# TinkerAccess_RFID_Adapter.net
KiCad netlist of a schematic drawn in EAGLE
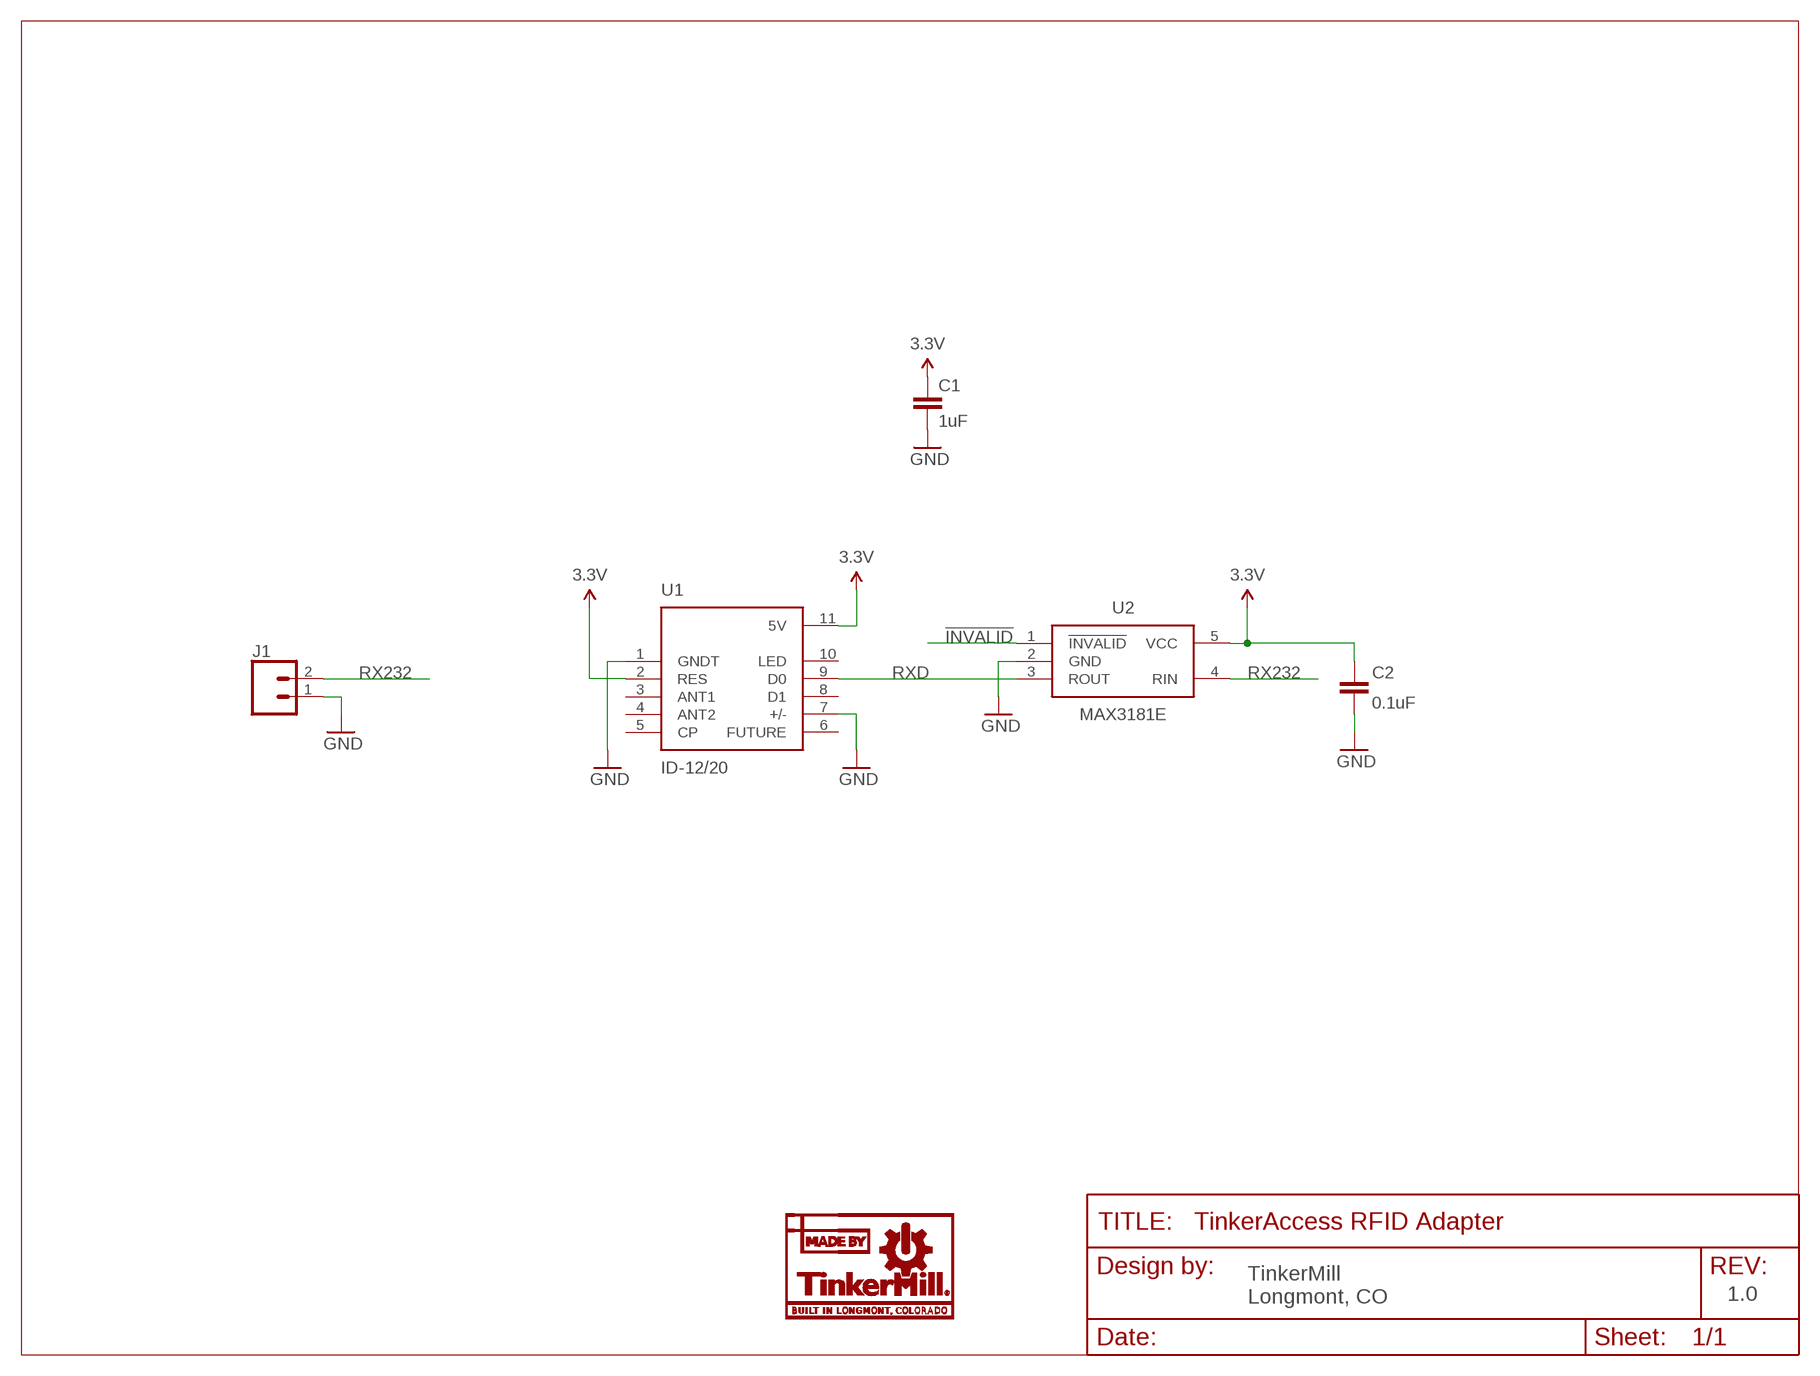
[diagram p0: schematic, sheet 1]

(export (version "E")
  (design (tool "Eeschema 10.0.6"))
  (components
    (comp (ref "C1")
      (value "1uF")
      (footprint "eagle-import:0603")
      (libsource (lib "eagle-import") (part "10UF-0603-6.3V-20%"))
    )
    (comp (ref "C2")
      (value "0.1uF")
      (footprint "eagle-import:0603")
      (fields (field (name "SPICEPREFIX") "C"))
      (libsource (lib "eagle-import") (part "0.1UF-0603-25V-(+80/-20%)"))
    )
    (comp (ref "J1")
      (value "CONN_025MM")
      (footprint "eagle-import:SCREWTERMINAL-5MM-2")
      (libsource (lib "eagle-import") (part "CONN_025MM"))
    )
    (comp (ref "LOGO1")
      (value "MADE_BY_TINKERMILL")
      (footprint "eagle-import:MADE_BY_TINKERMILL")
      (libsource (lib "eagle-import") (part "MADE_BY_TINKERMILL"))
    )
    (comp (ref "U1")
      (value "ID-12/20")
      (footprint "eagle-import:ID-12")
      (libsource (lib "eagle-import") (part "ID-12/20"))
    )
    (comp (ref "U2")
      (value "MAX3181E")
      (footprint "eagle-import:SOT23-5")
      (fields (field (name "SPICEPREFIX") "X"))
      (libsource (lib "eagle-import") (part "MAX3181E_SOT23-5"))
    )
  )
  (nets
    (net (code "1") (name "/RX232") (class "Default")
      (node (ref "J1") (pin "2") (pinfunction "2_2") (pintype "passive"))
      (node (ref "U2") (pin "4") (pinfunction "RIN_4") (pintype "bidirectional"))
    )
    (net (code "2") (name "/RXD") (class "Default")
      (node (ref "U1") (pin "9") (pinfunction "D0_9") (pintype "bidirectional"))
      (node (ref "U2") (pin "3") (pinfunction "ROUT_3") (pintype "bidirectional"))
    )
    (net (code "3") (name "/~{INVALID}") (class "Default")
      (node (ref "U2") (pin "1") (pinfunction "~{INVALID}_1") (pintype "bidirectional"))
    )
    (net (code "4") (name "3.3V") (class "Default")
      (node (ref "C1") (pin "1") (pinfunction "1_1") (pintype "passive"))
      (node (ref "C2") (pin "2") (pinfunction "2_2") (pintype "passive"))
      (node (ref "U1") (pin "11") (pinfunction "5V_11") (pintype "bidirectional"))
      (node (ref "U1") (pin "2") (pinfunction "RES_2") (pintype "bidirectional"))
      (node (ref "U2") (pin "5") (pinfunction "VCC_5") (pintype "bidirectional"))
    )
    (net (code "5") (name "GND") (class "Default")
      (node (ref "C1") (pin "2") (pinfunction "2_2") (pintype "passive"))
      (node (ref "C2") (pin "1") (pinfunction "1_1") (pintype "passive"))
      (node (ref "J1") (pin "1") (pinfunction "1_1") (pintype "passive"))
      (node (ref "U1") (pin "1") (pinfunction "GNDT_1") (pintype "bidirectional"))
      (node (ref "U1") (pin "7") (pinfunction "+/-_7") (pintype "bidirectional"))
      (node (ref "U2") (pin "2") (pinfunction "GND_2") (pintype "bidirectional"))
    )
    (net (code "6") (name "unconnected-(U1-ANT1-Pad3)") (class "Default")
      (node (ref "U1") (pin "3") (pinfunction "ANT1_3") (pintype "bidirectional"))
    )
    (net (code "7") (name "unconnected-(U1-ANT2-Pad4)") (class "Default")
      (node (ref "U1") (pin "4") (pinfunction "ANT2_4") (pintype "bidirectional"))
    )
    (net (code "8") (name "unconnected-(U1-CP-Pad5)") (class "Default")
      (node (ref "U1") (pin "5") (pinfunction "CP_5") (pintype "bidirectional"))
    )
    (net (code "9") (name "unconnected-(U1-D1-Pad8)") (class "Default")
      (node (ref "U1") (pin "8") (pinfunction "D1_8") (pintype "bidirectional"))
    )
    (net (code "10") (name "unconnected-(U1-FUTURE-Pad6)") (class "Default")
      (node (ref "U1") (pin "6") (pinfunction "FUTURE_6") (pintype "bidirectional"))
    )
    (net (code "11") (name "unconnected-(U1-LED-Pad10)") (class "Default")
      (node (ref "U1") (pin "10") (pinfunction "LED_10") (pintype "bidirectional"))
    )
  )
)
